# g5gate-wroom.net
KiCad netlist of a schematic drawn in EAGLE
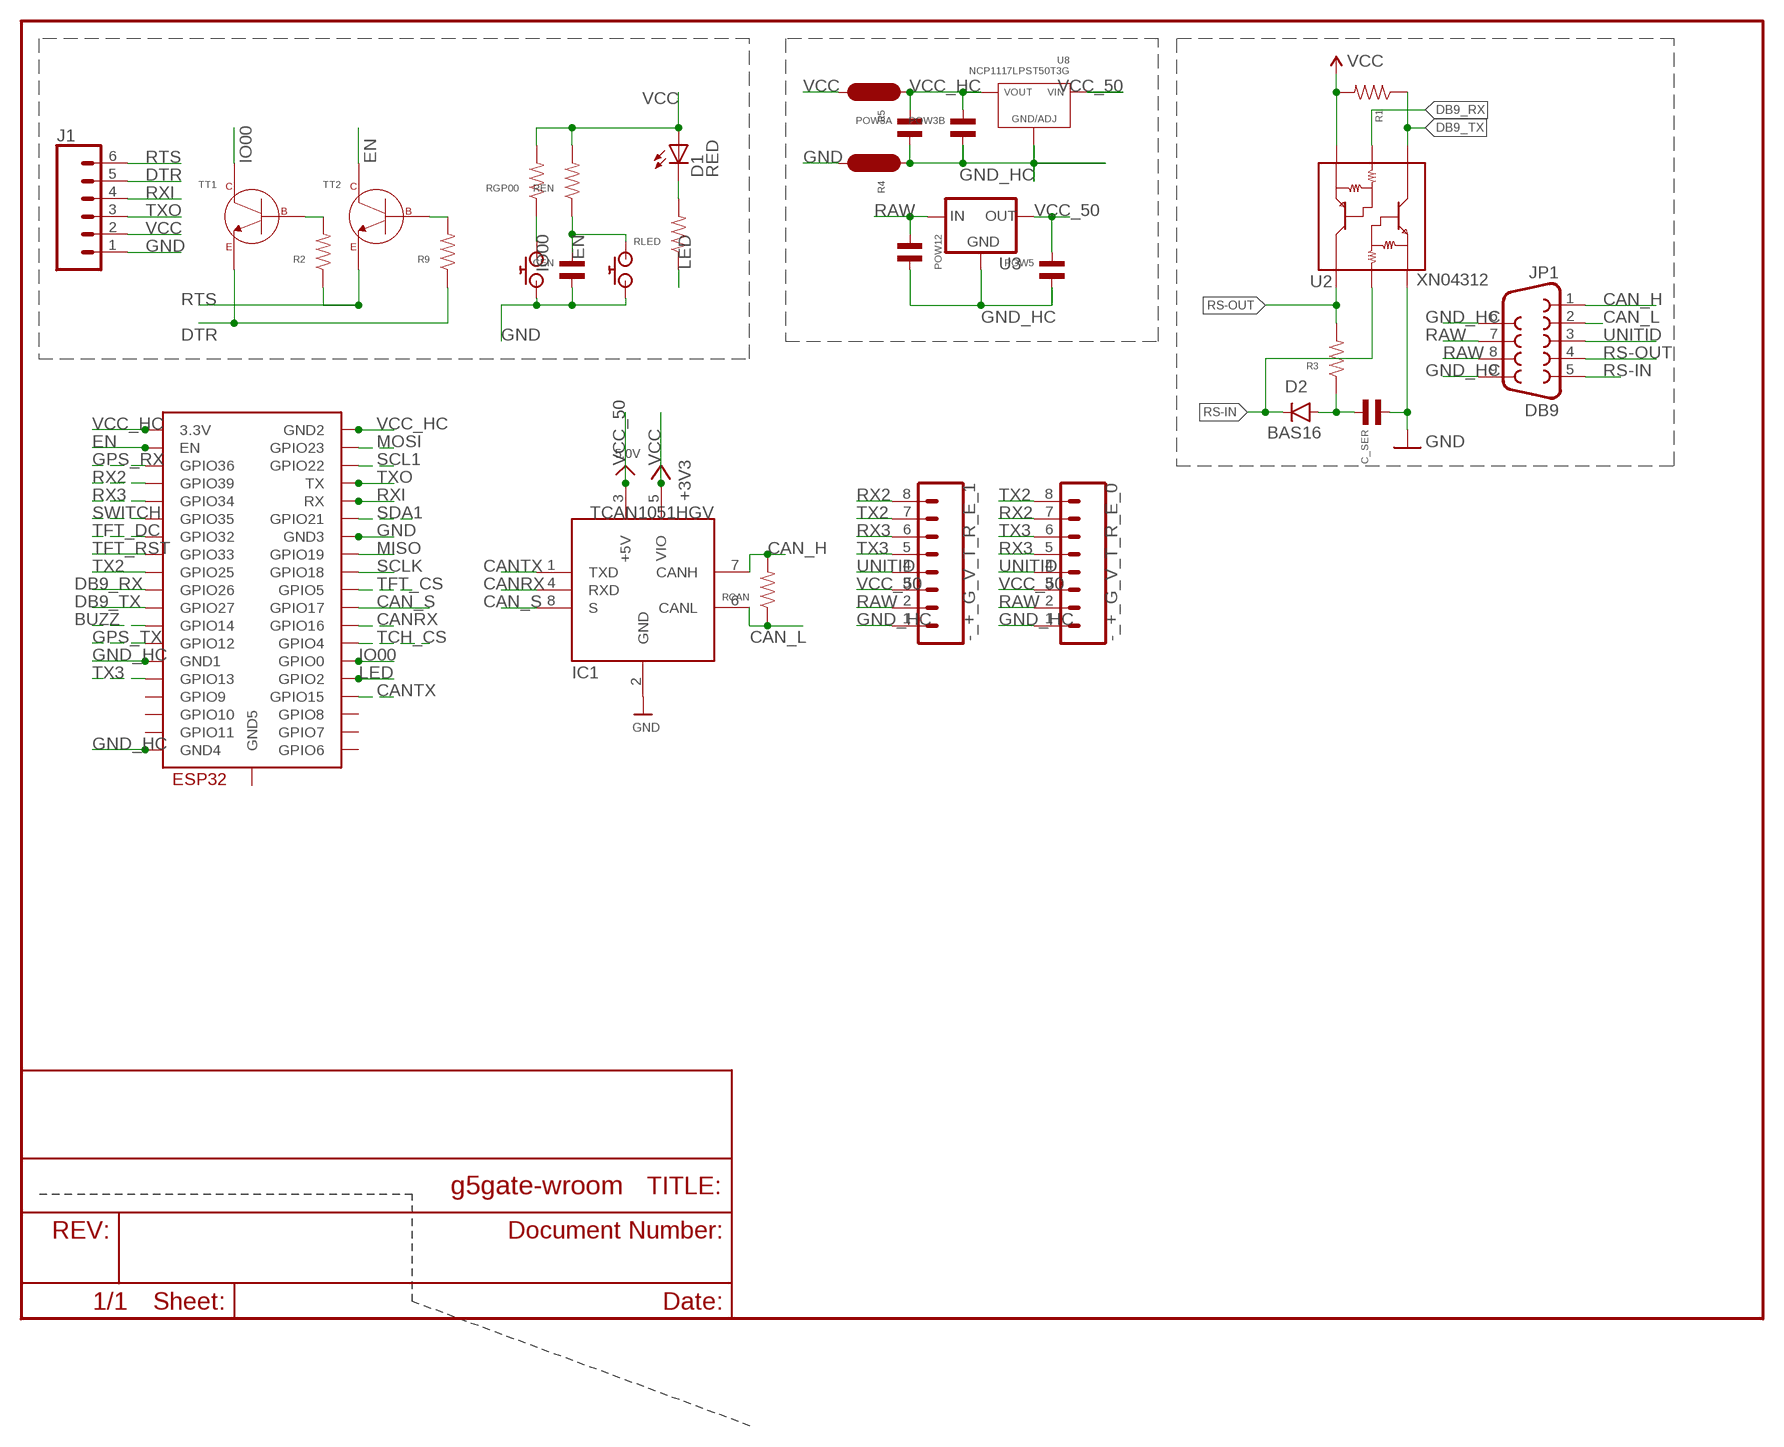
[diagram p0: schematic, sheet 1]

(export (version "E")
  (design (tool "Eeschema 10.0.6"))
  (components
    (comp (ref "-_+_G_V_T_R_E_0")
      (value "MF-CON-2.54mm-01x08")
      (footprint "eagle-import:1X08")
      (libsource (lib "eagle-import") (part "M081X08"))
    )
    (comp (ref "-_+_G_V_T_R_E_1")
      (value "MF-CON-2.54mm-01x08")
      (footprint "eagle-import:1X08")
      (libsource (lib "eagle-import") (part "M081X08"))
    )
    (comp (ref "CEN")
      (value "CAPACITOR_NP_0603")
      (footprint "eagle-import:C0603")
      (libsource (lib "eagle-import") (part "CAPACITOR_NP_0603"))
    )
    (comp (ref "C_SER")
      (value "CAPACITOR_NP_0603")
      (footprint "eagle-import:C0603")
      (libsource (lib "eagle-import") (part "CAPACITOR_NP_0603"))
    )
    (comp (ref "D1")
      (value "RED")
      (footprint "eagle-import:LED-0603")
      (libsource (lib "eagle-import") (part "LED-RED0603"))
    )
    (comp (ref "D2")
      (value "BAS16")
      (footprint "eagle-import:SOD-323")
      (libsource (lib "eagle-import") (part "DIODEBAS16"))
    )
    (comp (ref "IC1")
      (value "TCAN1051HGV")
      (footprint "eagle-import:SOIC8_150MIL")
      (libsource (lib "eagle-import") (part "CAN_TRANSCIEVER_TCAN1051V"))
    )
    (comp (ref "J1")
      (value "CONN_06")
      (footprint "eagle-import:1X6-1.25MM-SMD")
      (libsource (lib "eagle-import") (part "CONN_06"))
    )
    (comp (ref "JP1")
      (value "DB9")
      (footprint "eagle-import:DB9")
      (libsource (lib "eagle-import") (part "DB9FEMALE"))
    )
    (comp (ref "POW3A")
      (value "CAPACITOR_NP_0603")
      (footprint "eagle-import:C0603")
      (libsource (lib "eagle-import") (part "CAPACITOR_NP_0603"))
    )
    (comp (ref "POW3B")
      (value "CAPACITOR_NP_0603")
      (footprint "eagle-import:C0603")
      (libsource (lib "eagle-import") (part "CAPACITOR_NP_0603"))
    )
    (comp (ref "POW5")
      (value "CAPACITOR_NP_0603")
      (footprint "eagle-import:C0603")
      (libsource (lib "eagle-import") (part "CAPACITOR_NP_0603"))
    )
    (comp (ref "POW12")
      (value "CAPACITOR_NP_0603")
      (footprint "eagle-import:C0603")
      (libsource (lib "eagle-import") (part "CAPACITOR_NP_0603"))
    )
    (comp (ref "R1")
      (value "RESISTOR_0603")
      (footprint "eagle-import:R0603")
      (libsource (lib "eagle-import") (part "RESISTOR_0603"))
    )
    (comp (ref "R2")
      (value "RESISTOR_0603")
      (footprint "eagle-import:R0603")
      (libsource (lib "eagle-import") (part "RESISTOR_0603"))
    )
    (comp (ref "R3")
      (value "RESISTOR_0603")
      (footprint "eagle-import:R0603")
      (libsource (lib "eagle-import") (part "RESISTOR_0603"))
    )
    (comp (ref "R4")
      (value "JUMPER")
      (footprint "eagle-import:R0603_JMP")
      (libsource (lib "eagle-import") (part "JUMPER"))
    )
    (comp (ref "R5")
      (value "JUMPER")
      (footprint "eagle-import:R0603_JMP")
      (libsource (lib "eagle-import") (part "JUMPER"))
    )
    (comp (ref "R9")
      (value "RESISTOR_0603")
      (footprint "eagle-import:R0603")
      (libsource (lib "eagle-import") (part "RESISTOR_0603"))
    )
    (comp (ref "RCAN")
      (value "RESISTOR_0603")
      (footprint "eagle-import:R0603")
      (libsource (lib "eagle-import") (part "RESISTOR_0603"))
    )
    (comp (ref "REN")
      (value "RESISTOR_0603")
      (footprint "eagle-import:R0603")
      (libsource (lib "eagle-import") (part "RESISTOR_0603"))
    )
    (comp (ref "RGP00")
      (value "RESISTOR_0603")
      (footprint "eagle-import:R0603")
      (libsource (lib "eagle-import") (part "RESISTOR_0603"))
    )
    (comp (ref "RLED")
      (value "RESISTOR_0603")
      (footprint "eagle-import:R0603")
      (libsource (lib "eagle-import") (part "RESISTOR_0603"))
    )
    (comp (ref "TT1")
      (value "MF-DSC-SOT233-MMBT3904")
      (footprint "eagle-import:SOT-23-3")
      (fields (field (name "HOUSEPART") "YES"))
      (libsource (lib "eagle-import") (part "NPN_BJT_SOT-23-3MMBT3904"))
    )
    (comp (ref "TT2")
      (value "MF-DSC-SOT233-MMBT3904")
      (footprint "eagle-import:SOT-23-3")
      (fields (field (name "HOUSEPART") "YES"))
      (libsource (lib "eagle-import") (part "NPN_BJT_SOT-23-3MMBT3904"))
    )
    (comp (ref "U$1")
      (value "AMAZON_BUTTONB2010")
      (footprint "eagle-import:C2010")
      (libsource (lib "eagle-import") (part "AMAZON_BUTTONB2010"))
    )
    (comp (ref "U$2")
      (value "AMAZON_BUTTONB2010")
      (footprint "eagle-import:C2010")
      (libsource (lib "eagle-import") (part "AMAZON_BUTTONB2010"))
    )
    (comp (ref "U$3")
      (value "ESP32-WROOM")
      (footprint "eagle-import:ESP32-WROOM")
      (libsource (lib "eagle-import") (part "ESP32-WROOM"))
    )
    (comp (ref "U2")
      (value "XN04312")
      (footprint "eagle-import:SOT23-6")
      (libsource (lib "eagle-import") (part "XN04312SOT"))
    )
    (comp (ref "U3")
      (value "V_REG_78XXSINK")
      (footprint "eagle-import:TO220-IGO")
      (libsource (lib "eagle-import") (part "V_REG_78XXSINK"))
    )
    (comp (ref "U8")
      (value "NCP1117LPST50T3G")
      (footprint "eagle-import:SOT-223-3")
      (fields (field (name "HOUSEPART") "NO"))
      (libsource (lib "eagle-import") (part "NCP1117LPST50T3G"))
    )
  )
  (nets
    (net (code "1") (name "+3V3") (class "Default")
      (node (ref "D1") (pin "A") (pinfunction "A_A") (pintype "passive"))
      (node (ref "IC1") (pin "5") (pinfunction "VIO_5") (pintype "power_in"))
      (node (ref "J1") (pin "2") (pinfunction "2_2") (pintype "passive"))
      (node (ref "R1") (pin "P$2") (pinfunction "P$2_P$2") (pintype "passive"))
      (node (ref "R5") (pin "P$2") (pinfunction "P$2_P$2") (pintype "passive"))
      (node (ref "REN") (pin "P$2") (pinfunction "P$2_P$2") (pintype "passive"))
      (node (ref "RGP00") (pin "P$2") (pinfunction "P$2_P$2") (pintype "passive"))
      (node (ref "U2") (pin "3") (pinfunction "E2_3") (pintype "bidirectional"))
    )
    (net (code "2") (name "/BUZZ") (class "Default")
      (node (ref "U$3") (pin "IO14") (pinfunction "GPIO14_IO14") (pintype "bidirectional"))
    )
    (net (code "3") (name "/CANRX") (class "Default")
      (node (ref "IC1") (pin "4") (pinfunction "RXD_4") (pintype "output"))
      (node (ref "U$3") (pin "IO16") (pinfunction "GPIO16_IO16") (pintype "bidirectional"))
    )
    (net (code "4") (name "/CANTX") (class "Default")
      (node (ref "IC1") (pin "1") (pinfunction "TXD_1") (pintype "input"))
      (node (ref "U$3") (pin "IO15") (pinfunction "GPIO15_IO15") (pintype "bidirectional"))
    )
    (net (code "5") (name "/CAN_H") (class "Default")
      (node (ref "IC1") (pin "7") (pinfunction "CANH_7") (pintype "bidirectional"))
      (node (ref "JP1") (pin "1") (pinfunction "1_1") (pintype "passive"))
      (node (ref "RCAN") (pin "P$2") (pinfunction "P$2_P$2") (pintype "passive"))
    )
    (net (code "6") (name "/CAN_L") (class "Default")
      (node (ref "IC1") (pin "6") (pinfunction "CANL_6") (pintype "bidirectional"))
      (node (ref "JP1") (pin "2") (pinfunction "2_2") (pintype "passive"))
      (node (ref "RCAN") (pin "P$1") (pinfunction "P$1_P$1") (pintype "passive"))
    )
    (net (code "7") (name "/CAN_S") (class "Default")
      (node (ref "IC1") (pin "8") (pinfunction "S_8") (pintype "input"))
      (node (ref "U$3") (pin "IO17") (pinfunction "GPIO17_IO17") (pintype "bidirectional"))
    )
    (net (code "8") (name "/DTR") (class "Default")
      (node (ref "J1") (pin "5") (pinfunction "5_5") (pintype "passive"))
      (node (ref "R9") (pin "P$1") (pinfunction "P$1_P$1") (pintype "passive"))
      (node (ref "TT1") (pin "P$2") (pinfunction "EMITTER_P$2") (pintype "bidirectional"))
    )
    (net (code "9") (name "/EN") (class "Default")
      (node (ref "CEN") (pin "P$1") (pinfunction "P$1_P$1") (pintype "passive"))
      (node (ref "REN") (pin "P$1") (pinfunction "P$1_P$1") (pintype "passive"))
      (node (ref "TT2") (pin "P$3") (pinfunction "COLLECTOR_P$3") (pintype "bidirectional"))
      (node (ref "U$2") (pin "P$1") (pinfunction "P$1_P$1") (pintype "bidirectional"))
      (node (ref "U$3") (pin "EN") (pinfunction "EN_EN") (pintype "bidirectional"))
    )
    (net (code "10") (name "/GND_HC") (class "Default")
      (node (ref "-_+_G_V_T_R_E_0") (pin "1") (pinfunction "1_1") (pintype "passive"))
      (node (ref "-_+_G_V_T_R_E_1") (pin "1") (pinfunction "1_1") (pintype "passive"))
      (node (ref "JP1") (pin "6") (pinfunction "6_6") (pintype "passive"))
      (node (ref "JP1") (pin "9") (pinfunction "9_9") (pintype "passive"))
      (node (ref "POW12") (pin "P$2") (pinfunction "P$2_P$2") (pintype "passive"))
      (node (ref "POW3A") (pin "P$2") (pinfunction "P$2_P$2") (pintype "passive"))
      (node (ref "POW3B") (pin "P$2") (pinfunction "P$2_P$2") (pintype "passive"))
      (node (ref "POW5") (pin "P$2") (pinfunction "P$2_P$2") (pintype "passive"))
      (node (ref "R4") (pin "P$1") (pinfunction "P$1_P$1") (pintype "passive"))
      (node (ref "U$3") (pin "GND1") (pinfunction "GND1_GND1") (pintype "bidirectional"))
      (node (ref "U$3") (pin "GND4") (pinfunction "GND4_GND4") (pintype "bidirectional"))
      (node (ref "U3") (pin "GND") (pinfunction "GND_GND") (pintype "input"))
      (node (ref "U8") (pin "P$2") (pinfunction "GND/ADJ_P$2") (pintype "bidirectional"))
    )
    (net (code "11") (name "/GPS_RX") (class "Default")
      (node (ref "U$3") (pin "SENSOR_VP") (pinfunction "GPIO36_SENSOR_VP") (pintype "bidirectional"))
    )
    (net (code "12") (name "/GPS_TX") (class "Default")
      (node (ref "U$3") (pin "IO12") (pinfunction "GPIO12_IO12") (pintype "bidirectional"))
    )
    (net (code "13") (name "/IO00") (class "Default")
      (node (ref "RGP00") (pin "P$1") (pinfunction "P$1_P$1") (pintype "passive"))
      (node (ref "TT1") (pin "P$3") (pinfunction "COLLECTOR_P$3") (pintype "bidirectional"))
      (node (ref "U$1") (pin "P$1") (pinfunction "P$1_P$1") (pintype "bidirectional"))
      (node (ref "U$3") (pin "IO0") (pinfunction "GPIO0_IO0") (pintype "bidirectional"))
    )
    (net (code "14") (name "/LED") (class "Default")
      (node (ref "RLED") (pin "P$1") (pinfunction "P$1_P$1") (pintype "passive"))
      (node (ref "U$3") (pin "IO2") (pinfunction "GPIO2_IO2") (pintype "bidirectional"))
    )
    (net (code "15") (name "/MISO") (class "Default")
      (node (ref "U$3") (pin "IO19") (pinfunction "GPIO19_IO19") (pintype "bidirectional"))
    )
    (net (code "16") (name "/MOSI") (class "Default")
      (node (ref "U$3") (pin "IO23") (pinfunction "GPIO23_IO23") (pintype "bidirectional"))
    )
    (net (code "17") (name "/RAW") (class "Default")
      (node (ref "-_+_G_V_T_R_E_0") (pin "2") (pinfunction "2_2") (pintype "passive"))
      (node (ref "-_+_G_V_T_R_E_1") (pin "2") (pinfunction "2_2") (pintype "passive"))
      (node (ref "JP1") (pin "7") (pinfunction "7_7") (pintype "passive"))
      (node (ref "JP1") (pin "8") (pinfunction "8_8") (pintype "passive"))
      (node (ref "POW12") (pin "P$1") (pinfunction "P$1_P$1") (pintype "passive"))
      (node (ref "U3") (pin "IN") (pinfunction "IN_IN") (pintype "input"))
    )
    (net (code "18") (name "/RTS") (class "Default")
      (node (ref "J1") (pin "6") (pinfunction "6_6") (pintype "passive"))
      (node (ref "R2") (pin "P$1") (pinfunction "P$1_P$1") (pintype "passive"))
      (node (ref "TT2") (pin "P$2") (pinfunction "EMITTER_P$2") (pintype "bidirectional"))
    )
    (net (code "19") (name "/RX2") (class "Default")
      (node (ref "-_+_G_V_T_R_E_0") (pin "7") (pinfunction "7_7") (pintype "passive"))
      (node (ref "-_+_G_V_T_R_E_1") (pin "8") (pinfunction "8_8") (pintype "passive"))
      (node (ref "U$3") (pin "SENSOR_VN") (pinfunction "GPIO39_SENSOR_VN") (pintype "bidirectional"))
    )
    (net (code "20") (name "/RX3") (class "Default")
      (node (ref "-_+_G_V_T_R_E_0") (pin "5") (pinfunction "5_5") (pintype "passive"))
      (node (ref "-_+_G_V_T_R_E_1") (pin "6") (pinfunction "6_6") (pintype "passive"))
      (node (ref "U$3") (pin "IO34") (pinfunction "GPIO34_IO34") (pintype "bidirectional"))
    )
    (net (code "21") (name "/RXI") (class "Default")
      (node (ref "J1") (pin "4") (pinfunction "4_4") (pintype "passive"))
      (node (ref "U$3") (pin "RX") (pinfunction "RX_RX") (pintype "bidirectional"))
    )
    (net (code "22") (name "/SCL1") (class "Default")
      (node (ref "U$3") (pin "IO22") (pinfunction "GPIO22_IO22") (pintype "bidirectional"))
    )
    (net (code "23") (name "/SCLK") (class "Default")
      (node (ref "U$3") (pin "IO18") (pinfunction "GPIO18_IO18") (pintype "bidirectional"))
    )
    (net (code "24") (name "/SDA1") (class "Default")
      (node (ref "U$3") (pin "IO21") (pinfunction "GPIO21_IO21") (pintype "bidirectional"))
    )
    (net (code "25") (name "/SWITCH") (class "Default")
      (node (ref "U$3") (pin "IO35") (pinfunction "GPIO35_IO35") (pintype "bidirectional"))
    )
    (net (code "26") (name "/TCH_CS") (class "Default")
      (node (ref "U$3") (pin "IO4") (pinfunction "GPIO4_IO4") (pintype "bidirectional"))
    )
    (net (code "27") (name "/TFT_CS") (class "Default")
      (node (ref "U$3") (pin "IO5") (pinfunction "GPIO5_IO5") (pintype "bidirectional"))
    )
    (net (code "28") (name "/TFT_DC") (class "Default")
      (node (ref "U$3") (pin "IO32") (pinfunction "GPIO32_IO32") (pintype "bidirectional"))
    )
    (net (code "29") (name "/TFT_RST") (class "Default")
      (node (ref "U$3") (pin "IO33") (pinfunction "GPIO33_IO33") (pintype "bidirectional"))
    )
    (net (code "30") (name "/TX2") (class "Default")
      (node (ref "-_+_G_V_T_R_E_0") (pin "8") (pinfunction "8_8") (pintype "passive"))
      (node (ref "-_+_G_V_T_R_E_1") (pin "7") (pinfunction "7_7") (pintype "passive"))
      (node (ref "U$3") (pin "IO25") (pinfunction "GPIO25_IO25") (pintype "bidirectional"))
    )
    (net (code "31") (name "/TX3") (class "Default")
      (node (ref "-_+_G_V_T_R_E_0") (pin "6") (pinfunction "6_6") (pintype "passive"))
      (node (ref "-_+_G_V_T_R_E_1") (pin "5") (pinfunction "5_5") (pintype "passive"))
      (node (ref "U$3") (pin "IO13") (pinfunction "GPIO13_IO13") (pintype "bidirectional"))
    )
    (net (code "32") (name "/TXO") (class "Default")
      (node (ref "J1") (pin "3") (pinfunction "3_3") (pintype "passive"))
      (node (ref "U$3") (pin "TX") (pinfunction "TX_TX") (pintype "bidirectional"))
    )
    (net (code "33") (name "/UNITID") (class "Default")
      (node (ref "-_+_G_V_T_R_E_0") (pin "4") (pinfunction "4_4") (pintype "passive"))
      (node (ref "-_+_G_V_T_R_E_1") (pin "4") (pinfunction "4_4") (pintype "passive"))
      (node (ref "JP1") (pin "3") (pinfunction "3_3") (pintype "passive"))
    )
    (net (code "34") (name "/VCC_HC") (class "Default")
      (node (ref "POW3A") (pin "P$1") (pinfunction "P$1_P$1") (pintype "passive"))
      (node (ref "POW3B") (pin "P$1") (pinfunction "P$1_P$1") (pintype "passive"))
      (node (ref "R5") (pin "P$1") (pinfunction "P$1_P$1") (pintype "passive"))
      (node (ref "U$3") (pin "3V3") (pinfunction "3.3V_3V3") (pintype "bidirectional"))
      (node (ref "U$3") (pin "GND2") (pinfunction "GND2_GND2") (pintype "bidirectional"))
      (node (ref "U8") (pin "P$1") (pinfunction "VOUT_P$1") (pintype "bidirectional"))
      (node (ref "U8") (pin "P$3") (pinfunction "VOUT_P$3") (pintype "bidirectional"))
    )
    (net (code "35") (name "5.0V") (class "Default")
      (node (ref "-_+_G_V_T_R_E_0") (pin "3") (pinfunction "3_3") (pintype "passive"))
      (node (ref "-_+_G_V_T_R_E_1") (pin "3") (pinfunction "3_3") (pintype "passive"))
      (node (ref "IC1") (pin "3") (pinfunction "+5V_3") (pintype "power_in"))
      (node (ref "POW5") (pin "P$1") (pinfunction "P$1_P$1") (pintype "passive"))
      (node (ref "U3") (pin "OUT") (pinfunction "OUT_OUT") (pintype "passive"))
      (node (ref "U8") (pin "P$4") (pinfunction "VIN_P$4") (pintype "bidirectional"))
    )
    (net (code "36") (name "DB9_RX") (class "Default")
      (node (ref "U$3") (pin "IO26") (pinfunction "GPIO26_IO26") (pintype "bidirectional"))
      (node (ref "U2") (pin "2") (pinfunction "B2_2") (pintype "bidirectional"))
    )
    (net (code "37") (name "DB9_TX") (class "Default")
      (node (ref "R1") (pin "P$1") (pinfunction "P$1_P$1") (pintype "passive"))
      (node (ref "U$3") (pin "IO27") (pinfunction "GPIO27_IO27") (pintype "bidirectional"))
      (node (ref "U2") (pin "1") (pinfunction "C1_1") (pintype "bidirectional"))
    )
    (net (code "38") (name "GND") (class "Default")
      (node (ref "CEN") (pin "P$2") (pinfunction "P$2_P$2") (pintype "passive"))
      (node (ref "C_SER") (pin "P$2") (pinfunction "P$2_P$2") (pintype "passive"))
      (node (ref "IC1") (pin "2") (pinfunction "GND_2") (pintype "power_in"))
      (node (ref "J1") (pin "1") (pinfunction "1_1") (pintype "passive"))
      (node (ref "R4") (pin "P$2") (pinfunction "P$2_P$2") (pintype "passive"))
      (node (ref "U$1") (pin "P$2") (pinfunction "P$2_P$2") (pintype "bidirectional"))
      (node (ref "U$2") (pin "P$2") (pinfunction "P$2_P$2") (pintype "bidirectional"))
      (node (ref "U$3") (pin "GND3") (pinfunction "GND3_GND3") (pintype "bidirectional"))
      (node (ref "U2") (pin "6") (pinfunction "E1_6") (pintype "bidirectional"))
    )
    (net (code "39") (name "Net-(C_SER-PadP$1)") (class "Default")
      (node (ref "C_SER") (pin "P$1") (pinfunction "P$1_P$1") (pintype "passive"))
      (node (ref "D2") (pin "A") (pinfunction "A_A") (pintype "passive"))
      (node (ref "R3") (pin "P$1") (pinfunction "P$1_P$1") (pintype "passive"))
    )
    (net (code "40") (name "Net-(D1-PadC)") (class "Default")
      (node (ref "D1") (pin "C") (pinfunction "C_C") (pintype "passive"))
      (node (ref "RLED") (pin "P$2") (pinfunction "P$2_P$2") (pintype "passive"))
    )
    (net (code "41") (name "Net-(TT1-BASE)") (class "Default")
      (node (ref "R2") (pin "P$2") (pinfunction "P$2_P$2") (pintype "passive"))
      (node (ref "TT1") (pin "P$1") (pinfunction "BASE_P$1") (pintype "bidirectional"))
    )
    (net (code "42") (name "Net-(TT2-BASE)") (class "Default")
      (node (ref "R9") (pin "P$2") (pinfunction "P$2_P$2") (pintype "passive"))
      (node (ref "TT2") (pin "P$1") (pinfunction "BASE_P$1") (pintype "bidirectional"))
    )
    (net (code "43") (name "RS-IN") (class "Default")
      (node (ref "D2") (pin "C") (pinfunction "C_C") (pintype "passive"))
      (node (ref "JP1") (pin "5") (pinfunction "5_5") (pintype "passive"))
      (node (ref "U2") (pin "5") (pinfunction "B1_5") (pintype "bidirectional"))
    )
    (net (code "44") (name "RS-OUT") (class "Default")
      (node (ref "JP1") (pin "4") (pinfunction "4_4") (pintype "passive"))
      (node (ref "R3") (pin "P$2") (pinfunction "P$2_P$2") (pintype "passive"))
      (node (ref "U2") (pin "4") (pinfunction "C2_4") (pintype "bidirectional"))
    )
    (net (code "45") (name "unconnected-(U$3-GPIO6-PadCLK)") (class "Default")
      (node (ref "U$3") (pin "CLK") (pinfunction "GPIO6_CLK") (pintype "bidirectional"))
    )
    (net (code "46") (name "unconnected-(U$3-GPIO7-PadSD0)") (class "Default")
      (node (ref "U$3") (pin "SD0") (pinfunction "GPIO7_SD0") (pintype "bidirectional"))
    )
    (net (code "47") (name "unconnected-(U$3-GPIO8-PadSD1)") (class "Default")
      (node (ref "U$3") (pin "SD1") (pinfunction "GPIO8_SD1") (pintype "bidirectional"))
    )
    (net (code "48") (name "unconnected-(U$3-GPIO9-PadSD2)") (class "Default")
      (node (ref "U$3") (pin "SD2") (pinfunction "GPIO9_SD2") (pintype "bidirectional"))
    )
    (net (code "49") (name "unconnected-(U$3-GPIO10-PadSD3)") (class "Default")
      (node (ref "U$3") (pin "SD3") (pinfunction "GPIO10_SD3") (pintype "bidirectional"))
    )
    (net (code "50") (name "unconnected-(U$3-GPIO11-PadCMD)") (class "Default")
      (node (ref "U$3") (pin "CMD") (pinfunction "GPIO11_CMD") (pintype "bidirectional"))
    )
    (net (code "51") (name "unconnected-(U$3-PadGND5)") (class "Default")
      (node (ref "U$3") (pin "GND5") (pinfunction "GND5_GND5") (pintype "bidirectional"))
    )
  )
)
